# TP1SCH.net
KiCad netlist of a schematic drawn in Altium Designer
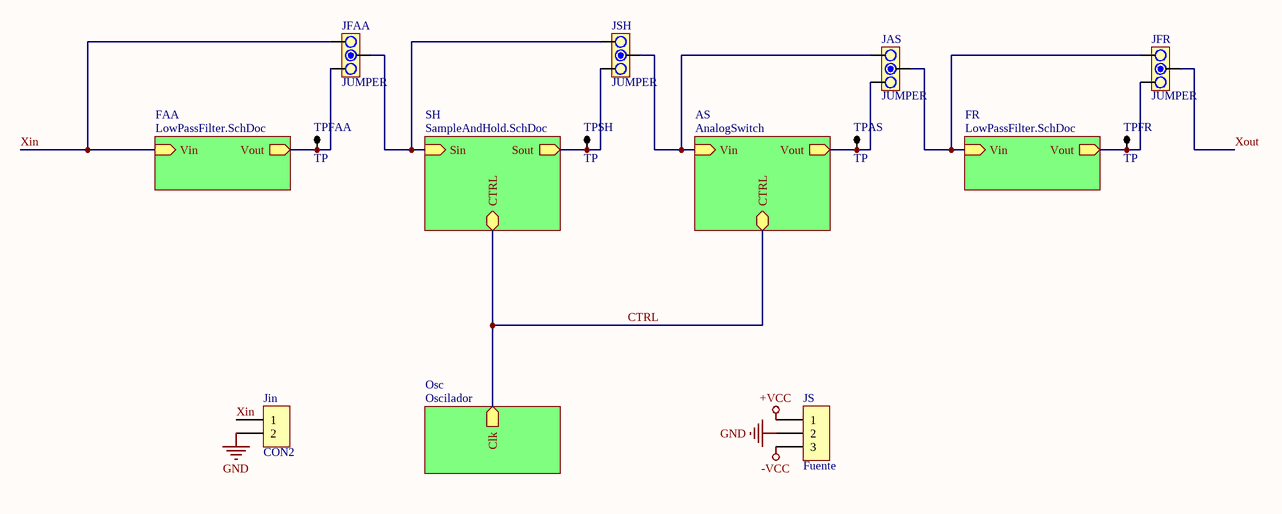
[diagram p0: TP1SCH.SchDoc]

(export (version "E")
  (design (tool "Eeschema 10.0.6"))
  (components
    (comp (ref "JAS") (value "JUMPER") (footprint "JUMPER3") (libsource (lib "Schematics") (part "JUMPER3")))
    (comp (ref "JFAA") (value "JUMPER") (footprint "JUMPER3") (libsource (lib "Schematics") (part "JUMPER3")))
    (comp (ref "JFR") (value "JUMPER") (footprint "JUMPER3") (libsource (lib "Schematics") (part "JUMPER3")))
    (comp (ref "Jin") (value "CON2") (footprint "SIP2") (libsource (lib "Schematics") (part "CON2")))
    (comp (ref "JS") (value "Fuente") (footprint "SIP3") (libsource (lib "Schematics") (part "CON3")))
    (comp (ref "JSH") (value "JUMPER") (footprint "JUMPER3") (libsource (lib "Schematics") (part "JUMPER3")))
    (comp (ref "TPAS") (value "TP") (footprint "TPTH") (libsource (lib "Schematics") (part "TP")))
    (comp (ref "TPFAA") (value "TP") (footprint "TPTH") (libsource (lib "Schematics") (part "TP")))
    (comp (ref "TPFR") (value "TP") (footprint "TPTH") (libsource (lib "Schematics") (part "TP")))
    (comp (ref "TPSH") (value "TP") (footprint "TPTH") (libsource (lib "Schematics") (part "TP")))
  )
  (nets
    (net (code "1") (name "+VCC") (class "Default")
      (node (ref "JS") (pin "1") (pinfunction "1_1") (pintype "passive"))
    )
    (net (code "2") (name "-VCC") (class "Default")
      (node (ref "JS") (pin "3") (pinfunction "3_3") (pintype "passive"))
    )
    (net (code "4") (name "/Sin") (class "Default")
      (node (ref "JFAA") (pin "2") (pinfunction "2_2") (pintype "passive"))
      (node (ref "JSH") (pin "3") (pinfunction "3_3") (pintype "passive"))
    )
    (net (code "5") (name "/Sout") (class "Default")
      (node (ref "JSH") (pin "1") (pinfunction "1_1") (pintype "passive"))
      (node (ref "TPSH") (pin "1") (pinfunction "1_1") (pintype "passive"))
    )
    (net (code "6") (name "/Vin") (class "Default")
      (node (ref "JAS") (pin "2") (pinfunction "2_2") (pintype "passive"))
      (node (ref "JFR") (pin "3") (pinfunction "3_3") (pintype "passive"))
    )
    (net (code "7") (name "/Vin_1") (class "Default")
      (node (ref "JAS") (pin "3") (pinfunction "3_3") (pintype "passive"))
      (node (ref "JSH") (pin "2") (pinfunction "2_2") (pintype "passive"))
    )
    (net (code "8") (name "/Vout") (class "Default")
      (node (ref "JFR") (pin "1") (pinfunction "1_1") (pintype "passive"))
      (node (ref "TPFR") (pin "1") (pinfunction "1_1") (pintype "passive"))
    )
    (net (code "9") (name "/Vout_1") (class "Default")
      (node (ref "JFAA") (pin "1") (pinfunction "1_1") (pintype "passive"))
      (node (ref "TPFAA") (pin "1") (pinfunction "1_1") (pintype "passive"))
    )
    (net (code "10") (name "/Vout_2") (class "Default")
      (node (ref "JAS") (pin "1") (pinfunction "1_1") (pintype "passive"))
      (node (ref "TPAS") (pin "1") (pinfunction "1_1") (pintype "passive"))
    )
    (net (code "11") (name "/Xin") (class "Default")
      (node (ref "JFAA") (pin "3") (pinfunction "3_3") (pintype "passive"))
      (node (ref "Jin") (pin "1") (pinfunction "1_1") (pintype "passive"))
    )
    (net (code "12") (name "/Xout") (class "Default")
      (node (ref "JFR") (pin "2") (pinfunction "2_2") (pintype "passive"))
    )
    (net (code "13") (name "GND") (class "Default")
      (node (ref "JS") (pin "2") (pinfunction "2_2") (pintype "passive"))
      (node (ref "Jin") (pin "2") (pinfunction "2_2") (pintype "passive"))
    )
  )
)
